# WiFI_Switch_v2.net
KiCad netlist of a schematic drawn in Altium Designer
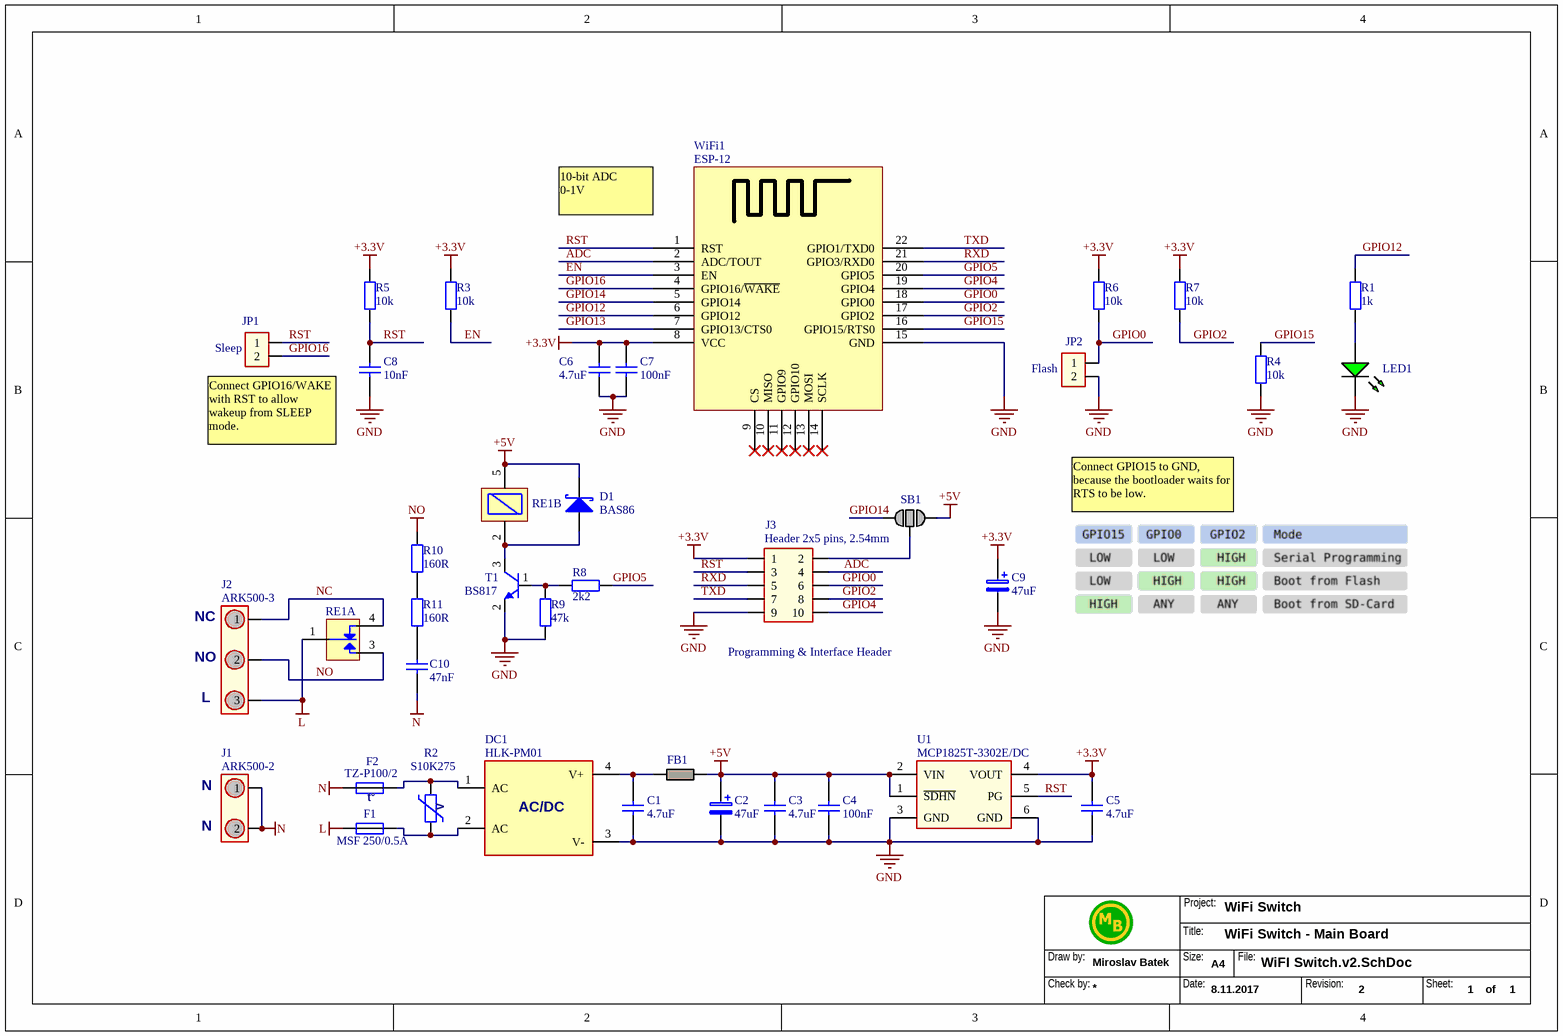
[diagram p0: WiFI Switch.v2.SchDoc]

(export (version "E")
  (design (tool "Eeschema 10.0.6"))
  (components
    (comp (ref "C1")
      (value "4.7uF")
      (footprint "SMD_C_0805_HAND")
      (description "Capacitor 4.7uF 0805")
      (fields (field (name "PART NUMBER") "CAP CER 0805 4.7uF 16V X7R 10%") (field (name "PUBLISHER") "JM"))
      (libsource (lib "Capacitors_0805") (part "CAPACITOR"))
    )
    (comp (ref "C2")
      (value "47uF")
      (footprint "TRH_CPOL_D6_3_RM2_5")
      (description "Capacitor 47uF, 16V, 6.3x5, polarised")
      (fields (field (name "PART NUMBER") "CAP POL 47uF 16V 105C 20%") (field (name "PUBLISHER") "MB"))
      (libsource (lib "My_Components") (part "CAPACITOR_POLARIZED"))
    )
    (comp (ref "C3")
      (value "4.7uF")
      (footprint "SMD_C_0805_HAND")
      (description "Capacitor 4.7uF 0805")
      (fields (field (name "PART NUMBER") "CAP CER 0805 4.7uF 16V X7R 10%") (field (name "PUBLISHER") "JM"))
      (libsource (lib "Capacitors_0805") (part "CAPACITOR"))
    )
    (comp (ref "C4")
      (value "100nF")
      (footprint "SMD_C_0805_HAND")
      (description "Capacitor 100nF 0805")
      (fields (field (name "PART NUMBER") "CAP CER 0805 100nF 50V X7R 10%") (field (name "PUBLISHER") "JM"))
      (libsource (lib "Capacitors_0805") (part "CAPACITOR"))
    )
    (comp (ref "C5")
      (value "4.7uF")
      (footprint "SMD_C_0805_HAND")
      (description "Capacitor 4.7uF 0805")
      (fields (field (name "PART NUMBER") "CAP CER 0805 4.7uF 16V X7R 10%") (field (name "PUBLISHER") "JM"))
      (libsource (lib "Capacitors_0805") (part "CAPACITOR"))
    )
    (comp (ref "C6")
      (value "4.7uF")
      (footprint "SMD_C_0805_HAND")
      (description "Capacitor 4.7uF 0805")
      (fields (field (name "PART NUMBER") "CAP CER 0805 4.7uF 16V X7R 10%") (field (name "PUBLISHER") "JM"))
      (libsource (lib "Capacitors_0805") (part "CAPACITOR"))
    )
    (comp (ref "C7")
      (value "100nF")
      (footprint "SMD_C_0805_HAND")
      (description "Capacitor 100nF 0805")
      (fields (field (name "PART NUMBER") "CAP CER 0805 100nF 50V X7R 10%") (field (name "PUBLISHER") "JM"))
      (libsource (lib "Capacitors_0805") (part "CAPACITOR"))
    )
    (comp (ref "C8")
      (value "10nF")
      (footprint "SMD_C_0805_HAND")
      (description "Capacitor 10nF 0805")
      (fields (field (name "PART NUMBER") "CAP CER 0805 10nF 50V X7R 10%") (field (name "PUBLISHER") "JM"))
      (libsource (lib "Capacitors_0805") (part "CAPACITOR"))
    )
    (comp (ref "C9")
      (value "47uF")
      (footprint "TRH_CPOL_D6_3_RM2_5")
      (description "Capacitor 47uF, 16V, 6.3x5, polarised")
      (fields (field (name "PART NUMBER") "CAP POL 47uF 16V 105C 20%") (field (name "PUBLISHER") "MB"))
      (libsource (lib "My_Components") (part "CAPACITOR_POLARIZED"))
    )
    (comp (ref "C10")
      (value "47nF")
      (footprint "TRH_C_17.5x5_RM15")
      (description "Capacitor 47nF, X2, 275V AC")
      (fields (field (name "PART NUMBER") "CFAC047N") (field (name "PUBLISHER") "MB"))
      (libsource (lib "My_Components") (part "CAPACITOR"))
    )
    (comp (ref "D1")
      (value "glass cylinder")
      (footprint "SMD_SOD80C")
      (description "DIODE, SCHOTTKY, 0.2A, 50V")
      (fields
        (field (name "PART NUMBER") "BAS86 SOD-80 0.2A 50V Shottky")
        (field (name "MANUFACTURER PART NUMBER") "BAS86")
        (field (name "PUBLISHER") "JM")
      )
      (libsource (lib "Diodes") (part "SHOTTKY_DIODE"))
    )
    (comp (ref "DC1") (value "HLK-PM01") (libsource (lib "HLK-PM01") (part "HLK-PM01")))
    (comp (ref "F1")
      (value "MSF 250/0.5A")
      (footprint "TRH_MSF250")
      (description "Fuse")
      (libsource (lib "My_Components") (part "Fuse"))
    )
    (comp (ref "F2")
      (value "TZ-P100/2")
      (footprint "TRH_TZ-Pxxx_2A")
      (description "Temperature Fuse 100C/2A")
      (fields (field (name "Comment") "FUSE_TEMP") (field (name "PUBLISHER") "MB"))
      (libsource (lib "My_Components") (part "FUSE_TEMP"))
    )
    (comp (ref "FB1")
      (value "Ferrite")
      (footprint "SMD_R_0805_HAND")
      (description "Ferite Bead 0805")
      (fields
        (field (name "PART NUMBER") "2508056017Y2")
        (field (name "MANUFACTURER") "FAIR-RITE")
        (field (name "PUBLISHER") "MB")
      )
      (libsource (lib "Miscellaneous") (part "Ferrite"))
    )
    (comp (ref "J1")
      (value "ARK500-2")
      (footprint "TRH_ARK500-2")
      (description "Terminal 2 (5mm)")
      (fields (field (name "Comment") "TERMINAL2") (field (name "PUBLISHER") "MB"))
      (libsource (lib "My_Components") (part "TERMINAL2"))
    )
    (comp (ref "J2")
      (value "ARK500-3")
      (footprint "TRH_ARK500-3")
      (description "Terminal 3 (5mm)")
      (fields (field (name "Comment") "TERMINAL3") (field (name "PUBLISHER") "MB"))
      (libsource (lib "My_Components") (part "TERMINAL3"))
    )
    (comp (ref "J3")
      (value "JUMPER5x2")
      (footprint "TRH_HDR2X05")
      (fields
        (field (name "PART NUMBER") "Header 2x5 pins, 2.54mm")
        (field (name "MANUFACTURER") "HARWIN")
        (field (name "MANUFACTURER PART NUMBER") "M20-9970546")
        (field (name "PUBLISHER") "ID")
      )
      (libsource (lib "Connectors") (part "JUMPER5x2"))
    )
    (comp (ref "JP1")
      (value "JUMPER2")
      (footprint "TRH_HDR1X02")
      (fields
        (field (name "PART NUMBER") "Header 1x2 pins, 2.54mm")
        (field (name "MANUFACTURER") "HARWIN")
        (field (name "MANUFACTURER PART NUMBER") "M20-9990246")
        (field (name "PUBLISHER") "ID")
      )
      (libsource (lib "Connectors") (part "JUMPER2"))
    )
    (comp (ref "JP2")
      (value "JUMPER2")
      (footprint "TRH_HDR1X02")
      (fields
        (field (name "PART NUMBER") "Header 1x2 pins, 2.54mm")
        (field (name "MANUFACTURER") "HARWIN")
        (field (name "MANUFACTURER PART NUMBER") "M20-9990246")
        (field (name "PUBLISHER") "ID")
      )
      (libsource (lib "Connectors") (part "JUMPER2"))
    )
    (comp (ref "LED1")
      (value "LED_GREEN")
      (footprint "SMD_LED_0805_HAND")
      (description "LED Green 0805, 2.40V@0.1mA")
      (fields (field (name "PART NUMBER") "LED GREEN 0805 450mcd 120°") (field (name "PUBLISHER") "RS"))
      (libsource (lib "Diodes") (part "LED_GREEN"))
    )
    (comp (ref "R1")
      (value "1k")
      (footprint "SMD_R_0805_HAND")
      (description "Resistor")
      (fields
        (field (name "PART NUMBER") "RES 0805 1k0 1% 1/10W")
        (field (name "MANUFACTURER") "MULTICOMP")
        (field (name "PUBLISHER") "ID")
      )
      (libsource (lib "Resistors_0805") (part "RESISTOR"))
    )
    (comp (ref "R2")
      (value "S10K275")
      (footprint "TRH_S10K275")
      (description "Varistor")
      (fields (field (name "PUBLISHER") "MB"))
      (libsource (lib "My_Components") (part "VARISTOR"))
    )
    (comp (ref "R3")
      (value "10k")
      (footprint "SMD_R_0805_HAND")
      (description "Resistor")
      (fields
        (field (name "PART NUMBER") "RES 0805 10k 1% 1/10W")
        (field (name "MANUFACTURER") "MULTICOMP")
        (field (name "PUBLISHER") "ID")
      )
      (libsource (lib "Resistors_0805") (part "RESISTOR"))
    )
    (comp (ref "R4")
      (value "10k")
      (footprint "SMD_R_0805_HAND")
      (description "Resistor")
      (fields
        (field (name "PART NUMBER") "RES 0805 10k 1% 1/10W")
        (field (name "MANUFACTURER") "MULTICOMP")
        (field (name "PUBLISHER") "ID")
      )
      (libsource (lib "") (part "RESISTOR_2"))
    )
    (comp (ref "R5")
      (value "10k")
      (footprint "SMD_R_0805_HAND")
      (description "Resistor")
      (fields
        (field (name "PART NUMBER") "RES 0805 10k 1% 1/10W")
        (field (name "MANUFACTURER") "MULTICOMP")
        (field (name "PUBLISHER") "ID")
      )
      (libsource (lib "Resistors_0805") (part "RESISTOR"))
    )
    (comp (ref "R6")
      (value "10k")
      (footprint "SMD_R_0805_HAND")
      (description "Resistor")
      (fields
        (field (name "PART NUMBER") "RES 0805 10k 1% 1/10W")
        (field (name "MANUFACTURER") "MULTICOMP")
        (field (name "PUBLISHER") "ID")
      )
      (libsource (lib "Resistors_0805") (part "RESISTOR"))
    )
    (comp (ref "R7")
      (value "10k")
      (footprint "SMD_R_0805_HAND")
      (description "Resistor")
      (fields
        (field (name "PART NUMBER") "RES 0805 10k 1% 1/10W")
        (field (name "MANUFACTURER") "MULTICOMP")
        (field (name "PUBLISHER") "ID")
      )
      (libsource (lib "Resistors_0805") (part "RESISTOR"))
    )
    (comp (ref "R8")
      (value "2k2")
      (footprint "SMD_R_0805_HAND")
      (description "Resistor")
      (fields
        (field (name "PART NUMBER") "RES 0805 2k2 1% 1/10W")
        (field (name "MANUFACTURER") "MULTICOMP")
        (field (name "PUBLISHER") "ID")
      )
      (libsource (lib "") (part "RESISTOR_1"))
    )
    (comp (ref "R9")
      (value "47k")
      (footprint "SMD_R_0805_HAND")
      (description "Resistor")
      (fields
        (field (name "PART NUMBER") "RES 0805 47k 1% 1/10W")
        (field (name "MANUFACTURER") "MULTICOMP")
        (field (name "PUBLISHER") "ID")
      )
      (libsource (lib "Resistors_0805") (part "RESISTOR"))
    )
    (comp (ref "R10")
      (value "160R")
      (footprint "SMD_R_1206_HAND")
      (description "Resistor")
      (fields
        (field (name "PART NUMBER") "RES 1206 160R 1% 0.25W")
        (field (name "Comment") "160R, 0.25W, 1%, SMD 1206")
        (field (name "PUBLISHER") "MB")
      )
      (libsource (lib "Resistors_1206") (part "RESISTOR"))
    )
    (comp (ref "R11")
      (value "160R")
      (footprint "SMD_R_1206_HAND")
      (description "Resistor")
      (fields
        (field (name "PART NUMBER") "RES 1206 160R 1% 0.25W")
        (field (name "Comment") "160R, 0.25W, 1%, SMD 1206")
        (field (name "PUBLISHER") "MB")
      )
      (libsource (lib "Resistors_1206") (part "RESISTOR"))
    )
    (comp (ref "RE1")
      (value "SRD-xxVDC-SL-C")
      (footprint "TRH_SRD-xxVDC-SL-C")
      (description "Rele 5V 250V/10A (ebay)")
      (fields (field (name "PART NUMBER") "SRD-5VDC-SL-C") (field (name "PUBLISHER") "MB"))
      (libsource (lib "My_Components") (part "SRD-xxVDC-SL-C"))
    )
    (comp (ref "SB1")
      (value "Solder Switch")
      (footprint "SOLDER_BRIDGE_SWITCH_SMALL")
      (fields (field (name "PART NUMBER") "Solder Bridge Switch Small") (field (name "PUBLISHER") "MB"))
      (libsource (lib "Miscellaneous") (part "SOLDER_BRIDGE_SWITCH"))
    )
    (comp (ref "T1")
      (value "BS817")
      (footprint "SMD_SOT23-3")
      (description "Transistor NPN SOT23-3")
      (fields (field (name "PART NUMBER") "BC817 NPN 45V 0.5A") (field (name "PUBLISHER") "JM"))
      (libsource (lib "Transistors") (part "NPN_(B1,E2,C3)"))
    )
    (comp (ref "U1")
      (value "MCP1825T-3302E/DC")
      (footprint "SMD_SOT223-5_HAND")
      (description "LDO 3.3V/500mA")
      (fields (field (name "Comment") "MCP1825T-xxxxE-DC") (field (name "PUBLISHER") "MB"))
      (libsource (lib "My_Components") (part "MCP1825T-xxxxE-DC"))
    )
    (comp (ref "WiFi1")
      (value "ESP-12")
      (footprint "SMD_ESP-12")
      (description "ESP8266 Module (ESP-12)")
      (fields (field (name "PUBLISHER") "MB"))
      (libsource (lib "My_Components") (part "ESP-12"))
    )
  )
  (nets
    (net (code "1") (name "+3.3V") (class "Default")
      (node (ref "C5") (pin "2") (pinfunction "2_2") (pintype "passive"))
      (node (ref "C6") (pin "2") (pinfunction "2_2") (pintype "passive"))
      (node (ref "C7") (pin "2") (pinfunction "2_2") (pintype "passive"))
      (node (ref "C9") (pin "1") (pinfunction "1_1") (pintype "passive"))
      (node (ref "J3") (pin "1") (pinfunction "1_1") (pintype "passive"))
      (node (ref "R3") (pin "2") (pinfunction "2_2") (pintype "passive"))
      (node (ref "R5") (pin "2") (pinfunction "2_2") (pintype "passive"))
      (node (ref "R6") (pin "2") (pinfunction "2_2") (pintype "passive"))
      (node (ref "R7") (pin "2") (pinfunction "2_2") (pintype "passive"))
      (node (ref "U1") (pin "4") (pinfunction "VOUT_4") (pintype "power_in"))
      (node (ref "WiFi1") (pin "8") (pinfunction "VCC_8") (pintype "passive"))
    )
    (net (code "2") (name "+5V") (class "Default")
      (node (ref "C2") (pin "1") (pinfunction "1_1") (pintype "passive"))
      (node (ref "C3") (pin "2") (pinfunction "2_2") (pintype "passive"))
      (node (ref "C4") (pin "2") (pinfunction "2_2") (pintype "passive"))
      (node (ref "D1") (pin "2") (pinfunction "K_2") (pintype "passive"))
      (node (ref "FB1") (pin "2") (pinfunction "2_2") (pintype "passive"))
      (node (ref "RE1") (pin "5") (pinfunction "COIL2_5") (pintype "passive"))
      (node (ref "SB1") (pin "3") (pinfunction "3_3") (pintype "passive"))
      (node (ref "U1") (pin "1") (pinfunction "~{SDHN}_1") (pintype "power_in"))
      (node (ref "U1") (pin "2") (pinfunction "VIN_2") (pintype "power_in"))
    )
    (net (code "3") (name "/ADC") (class "Default")
      (node (ref "J3") (pin "4") (pinfunction "4_4") (pintype "passive"))
      (node (ref "WiFi1") (pin "2") (pinfunction "ADC/TOUT_2") (pintype "passive"))
    )
    (net (code "4") (name "/EN") (class "Default")
      (node (ref "R3") (pin "1") (pinfunction "1_1") (pintype "passive"))
      (node (ref "WiFi1") (pin "3") (pinfunction "EN_3") (pintype "passive"))
    )
    (net (code "5") (name "/GPIO0") (class "Default")
      (node (ref "J3") (pin "6") (pinfunction "6_6") (pintype "passive"))
      (node (ref "JP2") (pin "1") (pinfunction "1_1") (pintype "passive"))
      (node (ref "R6") (pin "1") (pinfunction "1_1") (pintype "passive"))
      (node (ref "WiFi1") (pin "18") (pinfunction "GPIO0_18") (pintype "passive"))
    )
    (net (code "6") (name "/GPIO2") (class "Default")
      (node (ref "J3") (pin "8") (pinfunction "8_8") (pintype "passive"))
      (node (ref "R7") (pin "1") (pinfunction "1_1") (pintype "passive"))
      (node (ref "WiFi1") (pin "17") (pinfunction "GPIO2_17") (pintype "passive"))
    )
    (net (code "7") (name "/GPIO4") (class "Default")
      (node (ref "J3") (pin "10") (pinfunction "10_10") (pintype "passive"))
      (node (ref "WiFi1") (pin "19") (pinfunction "GPIO4_19") (pintype "passive"))
    )
    (net (code "8") (name "/GPIO5") (class "Default")
      (node (ref "R8") (pin "2") (pinfunction "2_2") (pintype "passive"))
      (node (ref "WiFi1") (pin "20") (pinfunction "GPIO5_20") (pintype "passive"))
    )
    (net (code "9") (name "/GPIO12") (class "Default")
      (node (ref "R1") (pin "2") (pinfunction "2_2") (pintype "passive"))
      (node (ref "WiFi1") (pin "6") (pinfunction "GPIO12_6") (pintype "passive"))
    )
    (net (code "10") (name "/GPIO13") (class "Default")
      (node (ref "WiFi1") (pin "7") (pinfunction "GPIO13/CTS0_7") (pintype "passive"))
    )
    (net (code "11") (name "/GPIO14") (class "Default")
      (node (ref "SB1") (pin "1") (pinfunction "1_1") (pintype "passive"))
      (node (ref "WiFi1") (pin "5") (pinfunction "GPIO14_5") (pintype "passive"))
    )
    (net (code "12") (name "/GPIO15") (class "Default")
      (node (ref "R4") (pin "1") (pinfunction "1_1") (pintype "passive"))
      (node (ref "WiFi1") (pin "16") (pinfunction "GPIO15/RTS0_16") (pintype "passive"))
    )
    (net (code "13") (name "/GPIO16") (class "Default")
      (node (ref "JP1") (pin "2") (pinfunction "2_2") (pintype "passive"))
      (node (ref "WiFi1") (pin "4") (pinfunction "GPIO16/~{WAKE}_4") (pintype "passive"))
    )
    (net (code "14") (name "/NC") (class "Default")
      (node (ref "J2") (pin "1") (pinfunction "1_1") (pintype "passive"))
      (node (ref "RE1") (pin "4") (pinfunction "NC_4") (pintype "passive"))
    )
    (net (code "15") (name "/RST") (class "Default")
      (node (ref "C8") (pin "2") (pinfunction "2_2") (pintype "passive"))
      (node (ref "J3") (pin "3") (pinfunction "3_3") (pintype "passive"))
      (node (ref "JP1") (pin "1") (pinfunction "1_1") (pintype "passive"))
      (node (ref "R5") (pin "1") (pinfunction "1_1") (pintype "passive"))
      (node (ref "U1") (pin "5") (pinfunction "PG_5") (pintype "power_in"))
      (node (ref "WiFi1") (pin "1") (pinfunction "RST_1") (pintype "passive"))
    )
    (net (code "16") (name "/RXD") (class "Default")
      (node (ref "J3") (pin "5") (pinfunction "5_5") (pintype "passive"))
      (node (ref "WiFi1") (pin "21") (pinfunction "GPIO3/RXD0_21") (pintype "passive"))
    )
    (net (code "17") (name "/TXD") (class "Default")
      (node (ref "J3") (pin "7") (pinfunction "7_7") (pintype "passive"))
      (node (ref "WiFi1") (pin "22") (pinfunction "GPIO1/TXD0_22") (pintype "passive"))
    )
    (net (code "18") (name "GND") (class "Default")
      (node (ref "C1") (pin "1") (pinfunction "1_1") (pintype "passive"))
      (node (ref "C2") (pin "2") (pinfunction "2_2") (pintype "passive"))
      (node (ref "C3") (pin "1") (pinfunction "1_1") (pintype "passive"))
      (node (ref "C4") (pin "1") (pinfunction "1_1") (pintype "passive"))
      (node (ref "C5") (pin "1") (pinfunction "1_1") (pintype "passive"))
      (node (ref "C6") (pin "1") (pinfunction "1_1") (pintype "passive"))
      (node (ref "C7") (pin "1") (pinfunction "1_1") (pintype "passive"))
      (node (ref "C8") (pin "1") (pinfunction "1_1") (pintype "passive"))
      (node (ref "C9") (pin "2") (pinfunction "2_2") (pintype "passive"))
      (node (ref "DC1") (pin "3") (pinfunction "V-_3") (pintype "passive"))
      (node (ref "J3") (pin "9") (pinfunction "9_9") (pintype "passive"))
      (node (ref "JP2") (pin "2") (pinfunction "2_2") (pintype "passive"))
      (node (ref "LED1") (pin "2") (pinfunction "K_2") (pintype "passive"))
      (node (ref "R4") (pin "2") (pinfunction "2_2") (pintype "passive"))
      (node (ref "R9") (pin "1") (pinfunction "1_1") (pintype "passive"))
      (node (ref "T1") (pin "2") (pinfunction "E_2") (pintype "passive"))
      (node (ref "U1") (pin "3") (pinfunction "GND_3") (pintype "power_in"))
      (node (ref "U1") (pin "6") (pinfunction "GND_6") (pintype "power_in"))
      (node (ref "WiFi1") (pin "15") (pinfunction "GND_15") (pintype "passive"))
    )
    (net (code "19") (name "L") (class "Default")
      (node (ref "F1") (pin "1") (pinfunction "1_1") (pintype "passive"))
      (node (ref "J2") (pin "3") (pinfunction "3_3") (pintype "passive"))
      (node (ref "RE1") (pin "1") (pinfunction "COMMON1_1") (pintype "passive"))
    )
    (net (code "20") (name "N") (class "Default")
      (node (ref "C10") (pin "1") (pinfunction "1_1") (pintype "passive"))
      (node (ref "F2") (pin "1") (pinfunction "1_1") (pintype "passive"))
      (node (ref "J1") (pin "1") (pinfunction "1_1") (pintype "passive"))
      (node (ref "J1") (pin "2") (pinfunction "2_2") (pintype "passive"))
    )
    (net (code "21") (name "NO") (class "Default")
      (node (ref "J2") (pin "2") (pinfunction "2_2") (pintype "passive"))
      (node (ref "R10") (pin "1") (pinfunction "1_1") (pintype "passive"))
      (node (ref "RE1") (pin "3") (pinfunction "NO_3") (pintype "passive"))
    )
    (net (code "22") (name "Net-(C10-Pad2)") (class "Default")
      (node (ref "C10") (pin "2") (pinfunction "2_2") (pintype "passive"))
      (node (ref "R11") (pin "2") (pinfunction "2_2") (pintype "passive"))
    )
    (net (code "23") (name "Net-(D1-A)") (class "Default")
      (node (ref "D1") (pin "1") (pinfunction "A_1") (pintype "passive"))
      (node (ref "RE1") (pin "2") (pinfunction "COIL1_2") (pintype "passive"))
      (node (ref "T1") (pin "3") (pinfunction "C_3") (pintype "passive"))
    )
    (net (code "24") (name "Net-(DC1-AC-Pad1)") (class "Default")
      (node (ref "DC1") (pin "1") (pinfunction "AC_1") (pintype "passive"))
      (node (ref "F2") (pin "2") (pinfunction "2_2") (pintype "passive"))
      (node (ref "R2") (pin "2") (pinfunction "2_2") (pintype "passive"))
    )
    (net (code "25") (name "Net-(DC1-AC-Pad2)") (class "Default")
      (node (ref "DC1") (pin "2") (pinfunction "AC_2") (pintype "passive"))
      (node (ref "F1") (pin "2") (pinfunction "2_2") (pintype "passive"))
      (node (ref "R2") (pin "1") (pinfunction "1_1") (pintype "passive"))
    )
    (net (code "26") (name "Net-(DC1-V+)") (class "Default")
      (node (ref "C1") (pin "2") (pinfunction "2_2") (pintype "passive"))
      (node (ref "DC1") (pin "4") (pinfunction "V+_4") (pintype "passive"))
      (node (ref "FB1") (pin "1") (pinfunction "1_1") (pintype "passive"))
    )
    (net (code "27") (name "Net-(J3-Pad2)") (class "Default")
      (node (ref "J3") (pin "2") (pinfunction "2_2") (pintype "passive"))
      (node (ref "SB1") (pin "2") (pinfunction "2_2") (pintype "passive"))
    )
    (net (code "28") (name "Net-(LED1-A)") (class "Default")
      (node (ref "LED1") (pin "1") (pinfunction "A_1") (pintype "passive"))
      (node (ref "R1") (pin "1") (pinfunction "1_1") (pintype "passive"))
    )
    (net (code "29") (name "Net-(R10-Pad2)") (class "Default")
      (node (ref "R10") (pin "2") (pinfunction "2_2") (pintype "passive"))
      (node (ref "R11") (pin "1") (pinfunction "1_1") (pintype "passive"))
    )
    (net (code "30") (name "Net-(T1-B)") (class "Default")
      (node (ref "R8") (pin "1") (pinfunction "1_1") (pintype "passive"))
      (node (ref "R9") (pin "2") (pinfunction "2_2") (pintype "passive"))
      (node (ref "T1") (pin "1") (pinfunction "B_1") (pintype "passive"))
    )
    (net (code "31") (name "unconnected-(WiFi1-CS-Pad9)") (class "Default")
      (node (ref "WiFi1") (pin "9") (pinfunction "CS_9") (pintype "passive+no_connect"))
    )
    (net (code "32") (name "unconnected-(WiFi1-GPIO9-Pad11)") (class "Default")
      (node (ref "WiFi1") (pin "11") (pinfunction "GPIO9_11") (pintype "passive+no_connect"))
    )
    (net (code "33") (name "unconnected-(WiFi1-GPIO10-Pad12)") (class "Default")
      (node (ref "WiFi1") (pin "12") (pinfunction "GPIO10_12") (pintype "passive+no_connect"))
    )
    (net (code "34") (name "unconnected-(WiFi1-MISO-Pad10)") (class "Default")
      (node (ref "WiFi1") (pin "10") (pinfunction "MISO_10") (pintype "passive+no_connect"))
    )
    (net (code "35") (name "unconnected-(WiFi1-MOSI-Pad13)") (class "Default")
      (node (ref "WiFi1") (pin "13") (pinfunction "MOSI_13") (pintype "passive+no_connect"))
    )
    (net (code "36") (name "unconnected-(WiFi1-SCLK-Pad14)") (class "Default")
      (node (ref "WiFi1") (pin "14") (pinfunction "SCLK_14") (pintype "passive+no_connect"))
    )
  )
)
